# Power.net
KiCad netlist of a schematic drawn in Altium Designer
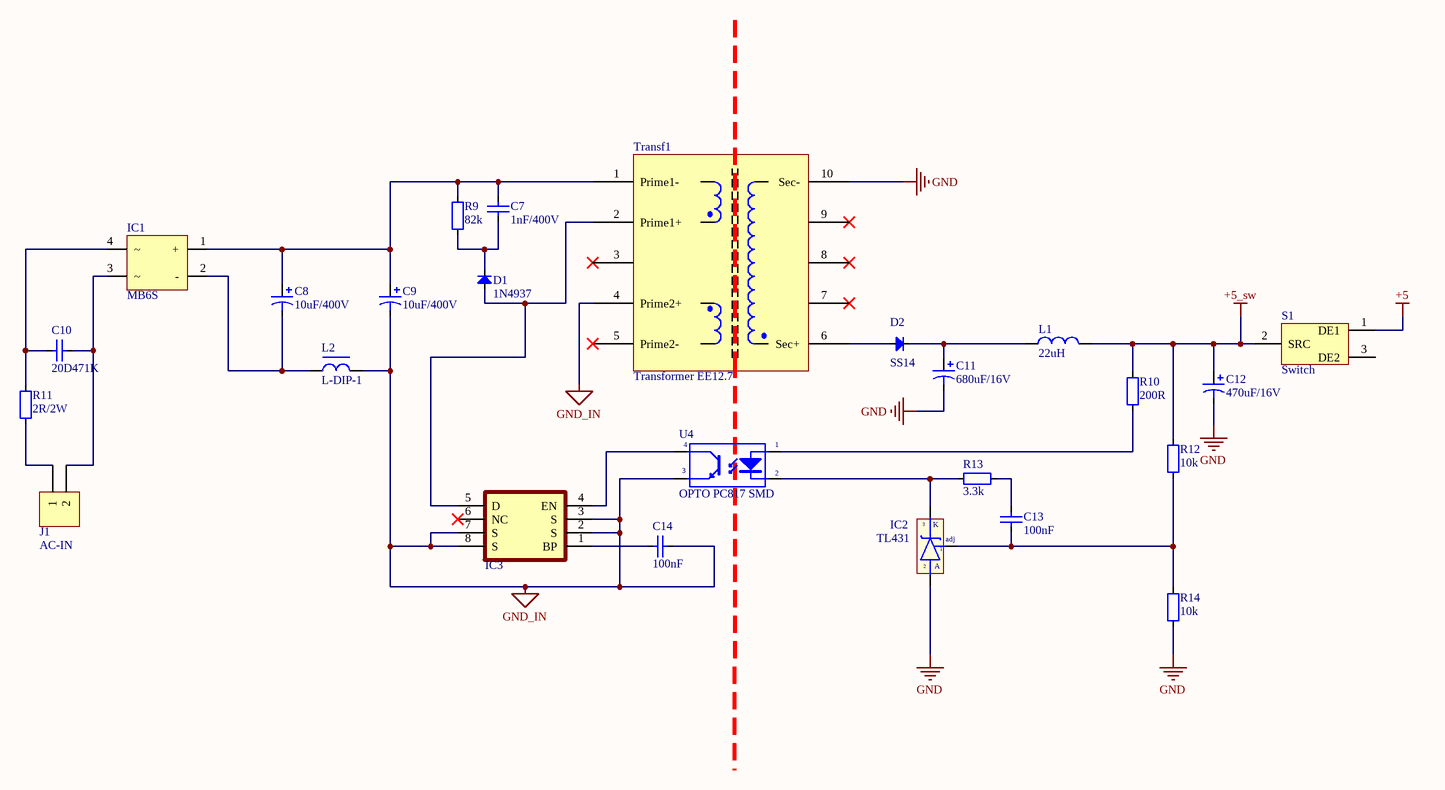
[diagram p0: Power.SchDoc]

(export (version "E")
  (design (tool "Eeschema 10.0.6"))
  (components
    (comp (ref "C7")
      (value "1nF/400V")
      (footprint "103/2KV")
      (description "CAP CERAMIC")
      (fields (field (name "PUBLISHER") "Altium Limited"))
      (libsource (lib "My Library") (part "Cap2KV"))
    )
    (comp (ref "C8")
      (value "10uF/400V")
      (footprint "C10mm")
      (description "Polarized Capacitor (Axial)")
      (fields (field (name "PUBLISHER") "Altium Limited"))
      (libsource (lib "My Library") (part "Cap Pol"))
    )
    (comp (ref "C9")
      (value "10uF/400V")
      (footprint "C10mm")
      (description "Polarized Capacitor (Axial)")
      (fields (field (name "PUBLISHER") "Altium Limited"))
      (libsource (lib "My Library") (part "Cap Pol"))
    )
    (comp (ref "C10")
      (value "20D471K")
      (footprint "103/2KV")
      (description "Varistor")
      (fields (field (name "PUBLISHER") "Altium Limited"))
      (libsource (lib "My Library") (part "Cap2KV"))
    )
    (comp (ref "C11")
      (value "680uF/16V")
      (footprint "C8mm")
      (description "Polarized Capacitor (Axial)")
      (fields (field (name "PUBLISHER") "Altium Limited"))
      (libsource (lib "My Library") (part "Cap Pol"))
    )
    (comp (ref "C12")
      (value "470uF/16V")
      (footprint "C8mm")
      (description "Polarized Capacitor (Axial)")
      (fields (field (name "PUBLISHER") "Altium Limited"))
      (libsource (lib "My Library") (part "Cap Pol"))
    )
    (comp (ref "C13")
      (value "100nF")
      (footprint "CAP_0805")
      (description "Capacitor")
      (fields (field (name "PUBLISHER") "Altium Limited"))
      (libsource (lib "My Library") (part "CapSMD"))
    )
    (comp (ref "C14")
      (value "100nF")
      (footprint "CAP_0805")
      (description "Capacitor")
      (fields (field (name "PUBLISHER") "Altium Limited"))
      (libsource (lib "My Library") (part "CapSMD"))
    )
    (comp (ref "D1")
      (value "1N4937")
      (footprint "DIO-1AN")
      (description "Diode Schottky\r\n1N4937")
      (fields (field (name "PUBLISHER") "Altium Limited"))
      (libsource (lib "My Library") (part "Diode SMD"))
    )
    (comp (ref "D2")
      (value "SS14")
      (footprint "DO-214AC(SMA)")
      (description "Diode Schottky\r\n1N5819")
      (fields (field (name "PUBLISHER") "Altium Limited"))
      (libsource (lib "My Library") (part "Diode SMD"))
    )
    (comp (ref "IC1") (value "MB6S") (footprint "MB6S") (libsource (lib "My Library") (part "MB6S")))
    (comp (ref "IC2")
      (value "TL431")
      (footprint "TL431_SOT")
      (description "Programmable Shunt Regulator")
      (libsource (lib "My Library") (part "TL431"))
    )
    (comp (ref "IC3")
      (value "TNY264")
      (footprint "DIP8")
      (description "Enhanced, Energy Efficient, Low Power Off-line Switcher")
      (libsource (lib "My Library") (part "TNY264"))
    )
    (comp (ref "J1")
      (value "AC-IN")
      (footprint "KF2-5.08")
      (fields
        (field (name "MANUFACTURER") "Würth Elektronik eiSos GmbH")
        (field (name "PARTNO") "691103110002")
        (field (name "CREATED BY") "Karrer Zheng")
      )
      (libsource (lib "My Library") (part "KF2"))
    )
    (comp (ref "L1")
      (value "22uH")
      (footprint "L_SMD")
      (description "CD73R 22uH 1.23A 7345")
      (libsource (lib "My Library") (part "Inductor"))
    )
    (comp (ref "L2")
      (value "L-DIP-1")
      (footprint "Inductor")
      (description "Inductor")
      (libsource (lib "My Library") (part "L-DIP-1"))
    )
    (comp (ref "R9")
      (value "82k")
      (footprint "RES-SMD-2512")
      (description "Resistor")
      (fields
        (field (name "MANUFACTURER") "Generic Components")
        (field (name "PUBLISHER") "Altium Hobart Technology Centre")
      )
      (libsource (lib "My Library") (part "Resistor - SMD"))
    )
    (comp (ref "R10")
      (value "200R")
      (footprint "RES-SMD-0805")
      (description "Resistor")
      (fields
        (field (name "MANUFACTURER") "Generic Components")
        (field (name "PUBLISHER") "Altium Hobart Technology Centre")
      )
      (libsource (lib "My Library") (part "Resistor - SMD"))
    )
    (comp (ref "R11")
      (value "2R/2W")
      (footprint "RES-1WW")
      (description "Resistor")
      (fields
        (field (name "MANUFACTURER") "Generic Components")
        (field (name "PUBLISHER") "Altium Hobart Technology Centre")
      )
      (libsource (lib "My Library") (part "Resistor - SMD"))
    )
    (comp (ref "R12")
      (value "10k")
      (footprint "RES-SMD-0805")
      (description "Resistor")
      (fields
        (field (name "MANUFACTURER") "Generic Components")
        (field (name "PUBLISHER") "Altium Hobart Technology Centre")
      )
      (libsource (lib "My Library") (part "Resistor - SMD"))
    )
    (comp (ref "R13")
      (value "3.3k")
      (footprint "RES-SMD-0805")
      (description "Resistor")
      (fields
        (field (name "MANUFACTURER") "Generic Components")
        (field (name "PUBLISHER") "Altium Hobart Technology Centre")
      )
      (libsource (lib "My Library") (part "Resistor - SMD"))
    )
    (comp (ref "R14")
      (value "10k")
      (footprint "RES-SMD-0805")
      (description "Resistor")
      (fields
        (field (name "MANUFACTURER") "Generic Components")
        (field (name "PUBLISHER") "Altium Hobart Technology Centre")
      )
      (libsource (lib "My Library") (part "Resistor - SMD"))
    )
    (comp (ref "S1") (value "Switch") (footprint "Switch") (libsource (lib "My Library") (part "Switch")))
    (comp (ref "Transf1")
      (value "Transformer EE12.7")
      (footprint "Transformer EE12.7")
      (libsource (lib "My Library") (part "Tranformer EE16"))
    )
    (comp (ref "U4")
      (value "OPTO PC817 SMD")
      (footprint "SOP4")
      (description "Single Opto")
      (libsource (lib "Altium_Lib_by_KhueNguyenCreator") (part "OPTO PC817 SMD"))
    )
  )
  (nets
    (net (code "1") (name "+5") (class "Default")
      (node (ref "S1") (pin "1") (pinfunction "DE1_1") (pintype "passive"))
    )
    (net (code "2") (name "+5_sw") (class "Default")
      (node (ref "C12") (pin "1") (pinfunction "1_1") (pintype "passive"))
      (node (ref "L1") (pin "2") (pinfunction "2_2") (pintype "passive"))
      (node (ref "R10") (pin "1") (pinfunction "1_1") (pintype "passive"))
      (node (ref "R12") (pin "1") (pinfunction "1_1") (pintype "passive"))
      (node (ref "S1") (pin "2") (pinfunction "SRC_2") (pintype "passive"))
    )
    (net (code "3") (name "GND") (class "Default")
      (node (ref "C11") (pin "2") (pinfunction "2_2") (pintype "passive"))
      (node (ref "C12") (pin "2") (pinfunction "2_2") (pintype "passive"))
      (node (ref "IC2") (pin "2") (pinfunction "A_2") (pintype "passive"))
      (node (ref "R14") (pin "2") (pinfunction "2_2") (pintype "passive"))
      (node (ref "Transf1") (pin "10") (pinfunction "Sec-_10") (pintype "passive"))
    )
    (net (code "4") (name "GND_IN") (class "Default")
      (node (ref "C14") (pin "1") (pinfunction "1_1") (pintype "passive"))
      (node (ref "C9") (pin "2") (pinfunction "2_2") (pintype "passive"))
      (node (ref "IC3") (pin "2") (pinfunction "S_2") (pintype "power_in"))
      (node (ref "IC3") (pin "3") (pinfunction "S_3") (pintype "power_in"))
      (node (ref "IC3") (pin "7") (pinfunction "S_7") (pintype "power_in"))
      (node (ref "IC3") (pin "8") (pinfunction "S_8") (pintype "power_in"))
      (node (ref "L2") (pin "2") (pinfunction "2_2") (pintype "passive"))
      (node (ref "Transf1") (pin "4") (pinfunction "Prime2+_4") (pintype "passive"))
      (node (ref "U4") (pin "3") (pinfunction "E_3") (pintype "passive"))
    )
    (net (code "5") (name "Net-(C10-Pad1)") (class "Default")
      (node (ref "C10") (pin "1") (pinfunction "1_1") (pintype "passive"))
      (node (ref "IC1") (pin "3") (pinfunction "~_3") (pintype "passive"))
      (node (ref "J1") (pin "2") (pinfunction "2_2") (pintype "passive"))
    )
    (net (code "6") (name "Net-(C10-Pad2)") (class "Default")
      (node (ref "C10") (pin "2") (pinfunction "2_2") (pintype "passive"))
      (node (ref "IC1") (pin "4") (pinfunction "~_4") (pintype "passive"))
      (node (ref "R11") (pin "1") (pinfunction "1_1") (pintype "passive"))
    )
    (net (code "7") (name "Net-(C13-Pad2)") (class "Default")
      (node (ref "C13") (pin "2") (pinfunction "2_2") (pintype "passive"))
      (node (ref "R13") (pin "2") (pinfunction "2_2") (pintype "passive"))
    )
    (net (code "8") (name "Net-(D1-A)") (class "Default")
      (node (ref "D1") (pin "1") (pinfunction "A_1") (pintype "passive"))
      (node (ref "IC3") (pin "5") (pinfunction "D_5") (pintype "power_in"))
      (node (ref "Transf1") (pin "2") (pinfunction "Prime1+_2") (pintype "passive"))
    )
    (net (code "9") (name "Net-(D1-K)") (class "Default")
      (node (ref "C7") (pin "2") (pinfunction "2_2") (pintype "passive"))
      (node (ref "D1") (pin "2") (pinfunction "K_2") (pintype "passive"))
      (node (ref "R9") (pin "2") (pinfunction "2_2") (pintype "passive"))
    )
    (net (code "10") (name "Net-(D2-A)") (class "Default")
      (node (ref "D2") (pin "1") (pinfunction "A_1") (pintype "passive"))
      (node (ref "Transf1") (pin "6") (pinfunction "Sec+_6") (pintype "passive"))
    )
    (net (code "11") (name "Net-(D2-K)") (class "Default")
      (node (ref "C11") (pin "1") (pinfunction "1_1") (pintype "passive"))
      (node (ref "D2") (pin "2") (pinfunction "K_2") (pintype "passive"))
      (node (ref "L1") (pin "1") (pinfunction "1_1") (pintype "passive"))
    )
    (net (code "12") (name "Net-(IC1-+)") (class "Default")
      (node (ref "C7") (pin "1") (pinfunction "1_1") (pintype "passive"))
      (node (ref "C8") (pin "1") (pinfunction "1_1") (pintype "passive"))
      (node (ref "C9") (pin "1") (pinfunction "1_1") (pintype "passive"))
      (node (ref "IC1") (pin "1") (pinfunction "+_1") (pintype "passive"))
      (node (ref "R9") (pin "1") (pinfunction "1_1") (pintype "passive"))
      (node (ref "Transf1") (pin "1") (pinfunction "Prime1-_1") (pintype "passive"))
    )
    (net (code "13") (name "Net-(IC1--)") (class "Default")
      (node (ref "C8") (pin "2") (pinfunction "2_2") (pintype "passive"))
      (node (ref "IC1") (pin "2") (pinfunction "-_2") (pintype "passive"))
      (node (ref "L2") (pin "1") (pinfunction "1_1") (pintype "passive"))
    )
    (net (code "14") (name "Net-(IC2-K)") (class "Default")
      (node (ref "IC2") (pin "3") (pinfunction "K_3") (pintype "passive"))
      (node (ref "R13") (pin "1") (pinfunction "1_1") (pintype "passive"))
      (node (ref "U4") (pin "2") (pinfunction "K_2") (pintype "passive"))
    )
    (net (code "15") (name "Net-(IC2-adj)") (class "Default")
      (node (ref "C13") (pin "1") (pinfunction "1_1") (pintype "passive"))
      (node (ref "IC2") (pin "1") (pinfunction "adj_1") (pintype "passive"))
      (node (ref "R12") (pin "2") (pinfunction "2_2") (pintype "passive"))
      (node (ref "R14") (pin "1") (pinfunction "1_1") (pintype "passive"))
    )
    (net (code "16") (name "Net-(IC3-BP)") (class "Default")
      (node (ref "C14") (pin "2") (pinfunction "2_2") (pintype "passive"))
      (node (ref "IC3") (pin "1") (pinfunction "BP_1") (pintype "power_in"))
    )
    (net (code "17") (name "Net-(IC3-EN)") (class "Default")
      (node (ref "IC3") (pin "4") (pinfunction "EN_4") (pintype "power_in"))
      (node (ref "U4") (pin "4") (pinfunction "C_4") (pintype "passive"))
    )
    (net (code "18") (name "Net-(J1-Pad1)") (class "Default")
      (node (ref "J1") (pin "1") (pinfunction "1_1") (pintype "passive"))
      (node (ref "R11") (pin "2") (pinfunction "2_2") (pintype "passive"))
    )
    (net (code "19") (name "Net-(U4-A)") (class "Default")
      (node (ref "R10") (pin "2") (pinfunction "2_2") (pintype "passive"))
      (node (ref "U4") (pin "1") (pinfunction "A_1") (pintype "passive"))
    )
    (net (code "20") (name "unconnected-(IC3-NC-Pad6)") (class "Default")
      (node (ref "IC3") (pin "6") (pinfunction "NC_6") (pintype "power_in+no_connect"))
    )
    (net (code "21") (name "unconnected-(S1-DE2-Pad3)") (class "Default")
      (node (ref "S1") (pin "3") (pinfunction "DE2_3") (pintype "passive"))
    )
    (net (code "22") (name "unconnected-(S1-Pad4)") (class "Default")
      (node (ref "S1") (pin "4") (pinfunction "4_4") (pintype "passive"))
    )
    (net (code "23") (name "unconnected-(S1-Pad5)") (class "Default")
      (node (ref "S1") (pin "5") (pinfunction "5_5") (pintype "passive"))
    )
    (net (code "24") (name "unconnected-(Transf1-Pad3)") (class "Default")
      (node (ref "Transf1") (pin "3") (pintype "passive+no_connect"))
    )
    (net (code "25") (name "unconnected-(Transf1-Pad7)") (class "Default")
      (node (ref "Transf1") (pin "7") (pintype "passive+no_connect"))
    )
    (net (code "26") (name "unconnected-(Transf1-Pad8)") (class "Default")
      (node (ref "Transf1") (pin "8") (pintype "passive+no_connect"))
    )
    (net (code "27") (name "unconnected-(Transf1-Pad9)") (class "Default")
      (node (ref "Transf1") (pin "9") (pintype "passive+no_connect"))
    )
    (net (code "28") (name "unconnected-(Transf1-Prime2--Pad5)") (class "Default")
      (node (ref "Transf1") (pin "5") (pinfunction "Prime2-_5") (pintype "passive+no_connect"))
    )
  )
)
